# ESP32_C3_MotorDriver.net
KiCad netlist of a schematic drawn in EAGLE
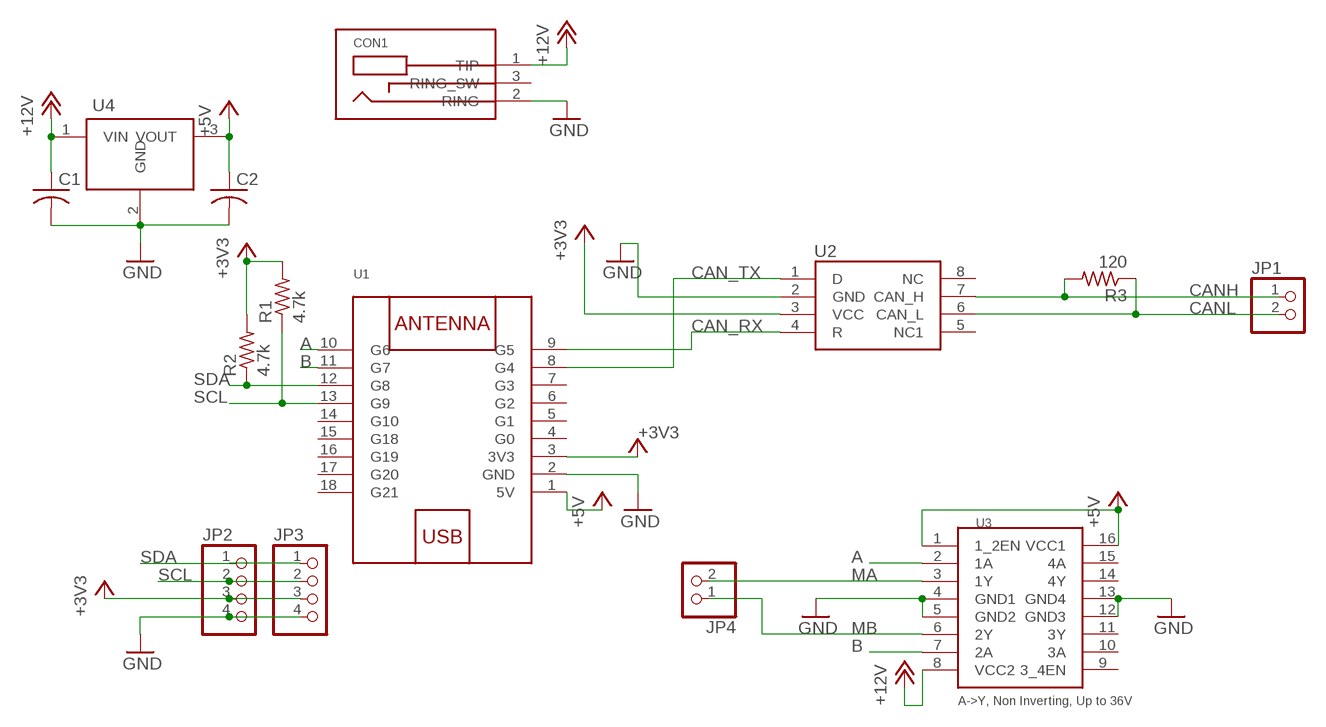
[diagram p0: schematic, sheet 1]

(export (version "E")
  (design (tool "Eeschema 10.0.6"))
  (components
    (comp (ref "C1")
      (value "C-USC0805")
      (footprint "eagle-import:C0805")
      (libsource (lib "eagle-import") (part "C-USC0805"))
    )
    (comp (ref "C2")
      (value "C-USC0805")
      (footprint "eagle-import:C0805")
      (libsource (lib "eagle-import") (part "C-USC0805"))
    )
    (comp (ref "CON1")
      (value "BARREL_JACK_3PINPJ-102A_2MM_HOLES")
      (footprint "eagle-import:PJ-102A_2MM_HOLES")
      (libsource (lib "eagle-import") (part "BARREL_JACK_3PINPJ-102A_2MM_HOLES"))
    )
    (comp (ref "JP1")
      (value "PINHD-1X2")
      (footprint "eagle-import:1X02")
      (libsource (lib "eagle-import") (part "PINHD-1X2"))
    )
    (comp (ref "JP2")
      (value "PINHD-1X4")
      (footprint "eagle-import:1X04")
      (libsource (lib "eagle-import") (part "PINHD-1X4"))
    )
    (comp (ref "JP3")
      (value "PINHD-1X4")
      (footprint "eagle-import:1X04")
      (libsource (lib "eagle-import") (part "PINHD-1X4"))
    )
    (comp (ref "JP4")
      (value "PINHD-1X2")
      (footprint "eagle-import:1X02")
      (libsource (lib "eagle-import") (part "PINHD-1X2"))
    )
    (comp (ref "R1")
      (value "4.7k")
      (footprint "eagle-import:M0805")
      (libsource (lib "eagle-import") (part "R-US_M0805"))
    )
    (comp (ref "R2")
      (value "4.7k")
      (footprint "eagle-import:M0805")
      (libsource (lib "eagle-import") (part "R-US_M0805"))
    )
    (comp (ref "R3")
      (value "120")
      (footprint "eagle-import:M0805")
      (libsource (lib "eagle-import") (part "R-US_M0805"))
    )
    (comp (ref "U1")
      (value "ESP32C3ZERO")
      (footprint "eagle-import:ESP32SUPERMINI_ESP32-SUPERMINI")
      (libsource (lib "eagle-import") (part "ESP32C3ZERO"))
    )
    (comp (ref "U2")
      (value "SN65HVD232DSOIC8")
      (footprint "eagle-import:SOIC-8")
      (libsource (lib "eagle-import") (part "SN65HVD232DSOIC8"))
    )
    (comp (ref "U3")
      (value "L293DDIP16")
      (footprint "eagle-import:DIP16_7.62MM")
      (libsource (lib "eagle-import") (part "L293DDIP16"))
    )
    (comp (ref "U4")
      (value "7805")
      (footprint "eagle-import:TO252-3")
      (libsource (lib "eagle-import") (part "7805"))
    )
  )
  (nets
    (net (code "1") (name "+3V3") (class "Default")
      (node (ref "JP2") (pin "3") (pinfunction "3_3") (pintype "passive"))
      (node (ref "JP3") (pin "3") (pinfunction "3_3") (pintype "passive"))
      (node (ref "R1") (pin "2") (pinfunction "2_2") (pintype "passive"))
      (node (ref "R2") (pin "2") (pinfunction "2_2") (pintype "passive"))
      (node (ref "U1") (pin "3") (pinfunction "3V3_3") (pintype "bidirectional"))
      (node (ref "U2") (pin "3") (pinfunction "VCC_3") (pintype "bidirectional"))
    )
    (net (code "2") (name "+5V") (class "Default")
      (node (ref "C2") (pin "1") (pinfunction "1_1") (pintype "passive"))
      (node (ref "U1") (pin "1") (pinfunction "5V_1") (pintype "power_in"))
      (node (ref "U3") (pin "1") (pinfunction "1_2EN_1") (pintype "bidirectional"))
      (node (ref "U3") (pin "16") (pinfunction "VCC1_16") (pintype "bidirectional"))
      (node (ref "U4") (pin "3") (pinfunction "VOUT_3") (pintype "bidirectional"))
    )
    (net (code "3") (name "+12V") (class "Default")
      (node (ref "C1") (pin "1") (pinfunction "1_1") (pintype "passive"))
      (node (ref "CON1") (pin "1") (pinfunction "TIP_1") (pintype "bidirectional"))
      (node (ref "U3") (pin "8") (pinfunction "VCC2_8") (pintype "bidirectional"))
      (node (ref "U4") (pin "1") (pinfunction "VIN_1") (pintype "bidirectional"))
    )
    (net (code "4") (name "/A") (class "Default")
      (node (ref "U1") (pin "10") (pinfunction "G6_10") (pintype "bidirectional"))
      (node (ref "U3") (pin "2") (pinfunction "1A_2") (pintype "bidirectional"))
    )
    (net (code "5") (name "/B") (class "Default")
      (node (ref "U1") (pin "11") (pinfunction "G7_11") (pintype "bidirectional"))
      (node (ref "U3") (pin "7") (pinfunction "2A_7") (pintype "bidirectional"))
    )
    (net (code "6") (name "/CANH") (class "Default")
      (node (ref "JP1") (pin "1") (pinfunction "1_1") (pintype "passive"))
      (node (ref "R3") (pin "2") (pinfunction "2_2") (pintype "passive"))
      (node (ref "U2") (pin "7") (pinfunction "CAN_H_7") (pintype "bidirectional"))
    )
    (net (code "7") (name "/CANL") (class "Default")
      (node (ref "JP1") (pin "2") (pinfunction "2_2") (pintype "passive"))
      (node (ref "R3") (pin "1") (pinfunction "1_1") (pintype "passive"))
      (node (ref "U2") (pin "6") (pinfunction "CAN_L_6") (pintype "bidirectional"))
    )
    (net (code "8") (name "/CAN_RX") (class "Default")
      (node (ref "U1") (pin "9") (pinfunction "G5_9") (pintype "bidirectional"))
      (node (ref "U2") (pin "4") (pinfunction "R_4") (pintype "bidirectional"))
    )
    (net (code "9") (name "/CAN_TX") (class "Default")
      (node (ref "U1") (pin "8") (pinfunction "G4_8") (pintype "bidirectional"))
      (node (ref "U2") (pin "1") (pinfunction "D_1") (pintype "bidirectional"))
    )
    (net (code "10") (name "/G19") (class "Default")
      (node (ref "U1") (pin "16") (pinfunction "G19_16") (pintype "power_in"))
    )
    (net (code "11") (name "/MA") (class "Default")
      (node (ref "JP4") (pin "2") (pinfunction "2_2") (pintype "passive"))
      (node (ref "U3") (pin "3") (pinfunction "1Y_3") (pintype "bidirectional"))
    )
    (net (code "12") (name "/MB") (class "Default")
      (node (ref "JP4") (pin "1") (pinfunction "1_1") (pintype "passive"))
      (node (ref "U3") (pin "6") (pinfunction "2Y_6") (pintype "bidirectional"))
    )
    (net (code "13") (name "/SCL") (class "Default")
      (node (ref "JP2") (pin "2") (pinfunction "2_2") (pintype "passive"))
      (node (ref "JP3") (pin "2") (pinfunction "2_2") (pintype "passive"))
      (node (ref "R1") (pin "1") (pinfunction "1_1") (pintype "passive"))
      (node (ref "U1") (pin "13") (pinfunction "G9_13") (pintype "bidirectional"))
    )
    (net (code "14") (name "/SDA") (class "Default")
      (node (ref "JP2") (pin "1") (pinfunction "1_1") (pintype "passive"))
      (node (ref "JP3") (pin "1") (pinfunction "1_1") (pintype "passive"))
      (node (ref "R2") (pin "1") (pinfunction "1_1") (pintype "passive"))
      (node (ref "U1") (pin "12") (pinfunction "G8_12") (pintype "bidirectional"))
    )
    (net (code "15") (name "GND") (class "Default")
      (node (ref "C1") (pin "2") (pinfunction "2_2") (pintype "passive"))
      (node (ref "C2") (pin "2") (pinfunction "2_2") (pintype "passive"))
      (node (ref "CON1") (pin "2") (pinfunction "RING_2") (pintype "bidirectional"))
      (node (ref "JP2") (pin "4") (pinfunction "4_4") (pintype "passive"))
      (node (ref "JP3") (pin "4") (pinfunction "4_4") (pintype "passive"))
      (node (ref "U1") (pin "2") (pinfunction "GND_2") (pintype "power_in"))
      (node (ref "U2") (pin "2") (pinfunction "GND_2") (pintype "bidirectional"))
      (node (ref "U3") (pin "12") (pinfunction "GND3_12") (pintype "bidirectional"))
      (node (ref "U3") (pin "13") (pinfunction "GND4_13") (pintype "bidirectional"))
      (node (ref "U3") (pin "4") (pinfunction "GND1_4") (pintype "bidirectional"))
      (node (ref "U3") (pin "5") (pinfunction "GND2_5") (pintype "bidirectional"))
      (node (ref "U4") (pin "2") (pinfunction "GND_2") (pintype "bidirectional"))
    )
    (net (code "16") (name "unconnected-(CON1-RING_SW-Pad3)") (class "Default")
      (node (ref "CON1") (pin "3") (pinfunction "RING_SW_3") (pintype "bidirectional"))
    )
    (net (code "17") (name "unconnected-(U1-G0-Pad4)") (class "Default")
      (node (ref "U1") (pin "4") (pinfunction "G0_4") (pintype "bidirectional"))
    )
    (net (code "18") (name "unconnected-(U1-G1-Pad5)") (class "Default")
      (node (ref "U1") (pin "5") (pinfunction "G1_5") (pintype "bidirectional"))
    )
    (net (code "19") (name "unconnected-(U1-G2-Pad6)") (class "Default")
      (node (ref "U1") (pin "6") (pinfunction "G2_6") (pintype "bidirectional"))
    )
    (net (code "20") (name "unconnected-(U1-G3-Pad7)") (class "Default")
      (node (ref "U1") (pin "7") (pinfunction "G3_7") (pintype "bidirectional"))
    )
    (net (code "21") (name "unconnected-(U1-G10-Pad14)") (class "Default")
      (node (ref "U1") (pin "14") (pinfunction "G10_14") (pintype "bidirectional"))
    )
    (net (code "22") (name "unconnected-(U1-G18-Pad15)") (class "Default")
      (node (ref "U1") (pin "15") (pinfunction "G18_15") (pintype "bidirectional"))
    )
    (net (code "23") (name "unconnected-(U1-G20-Pad17)") (class "Default")
      (node (ref "U1") (pin "17") (pinfunction "G20_17") (pintype "bidirectional"))
    )
    (net (code "24") (name "unconnected-(U1-G21-Pad18)") (class "Default")
      (node (ref "U1") (pin "18") (pinfunction "G21_18") (pintype "bidirectional"))
    )
    (net (code "25") (name "unconnected-(U2-NC-Pad8)") (class "Default")
      (node (ref "U2") (pin "8") (pinfunction "NC_8") (pintype "bidirectional"))
    )
    (net (code "26") (name "unconnected-(U2-NC1-Pad5)") (class "Default")
      (node (ref "U2") (pin "5") (pinfunction "NC1_5") (pintype "bidirectional"))
    )
    (net (code "27") (name "unconnected-(U3-3A-Pad10)") (class "Default")
      (node (ref "U3") (pin "10") (pinfunction "3A_10") (pintype "bidirectional"))
    )
    (net (code "28") (name "unconnected-(U3-3Y-Pad11)") (class "Default")
      (node (ref "U3") (pin "11") (pinfunction "3Y_11") (pintype "bidirectional"))
    )
    (net (code "29") (name "unconnected-(U3-3_4EN-Pad9)") (class "Default")
      (node (ref "U3") (pin "9") (pinfunction "3_4EN_9") (pintype "bidirectional"))
    )
    (net (code "30") (name "unconnected-(U3-4A-Pad15)") (class "Default")
      (node (ref "U3") (pin "15") (pinfunction "4A_15") (pintype "bidirectional"))
    )
    (net (code "31") (name "unconnected-(U3-4Y-Pad14)") (class "Default")
      (node (ref "U3") (pin "14") (pinfunction "4Y_14") (pintype "bidirectional"))
    )
  )
)
